# S7CAS-PLEIADES-CARTE-MERE_Pxx_ARBRE_CAP_.net
KiCad netlist of a schematic drawn in Altium Designer
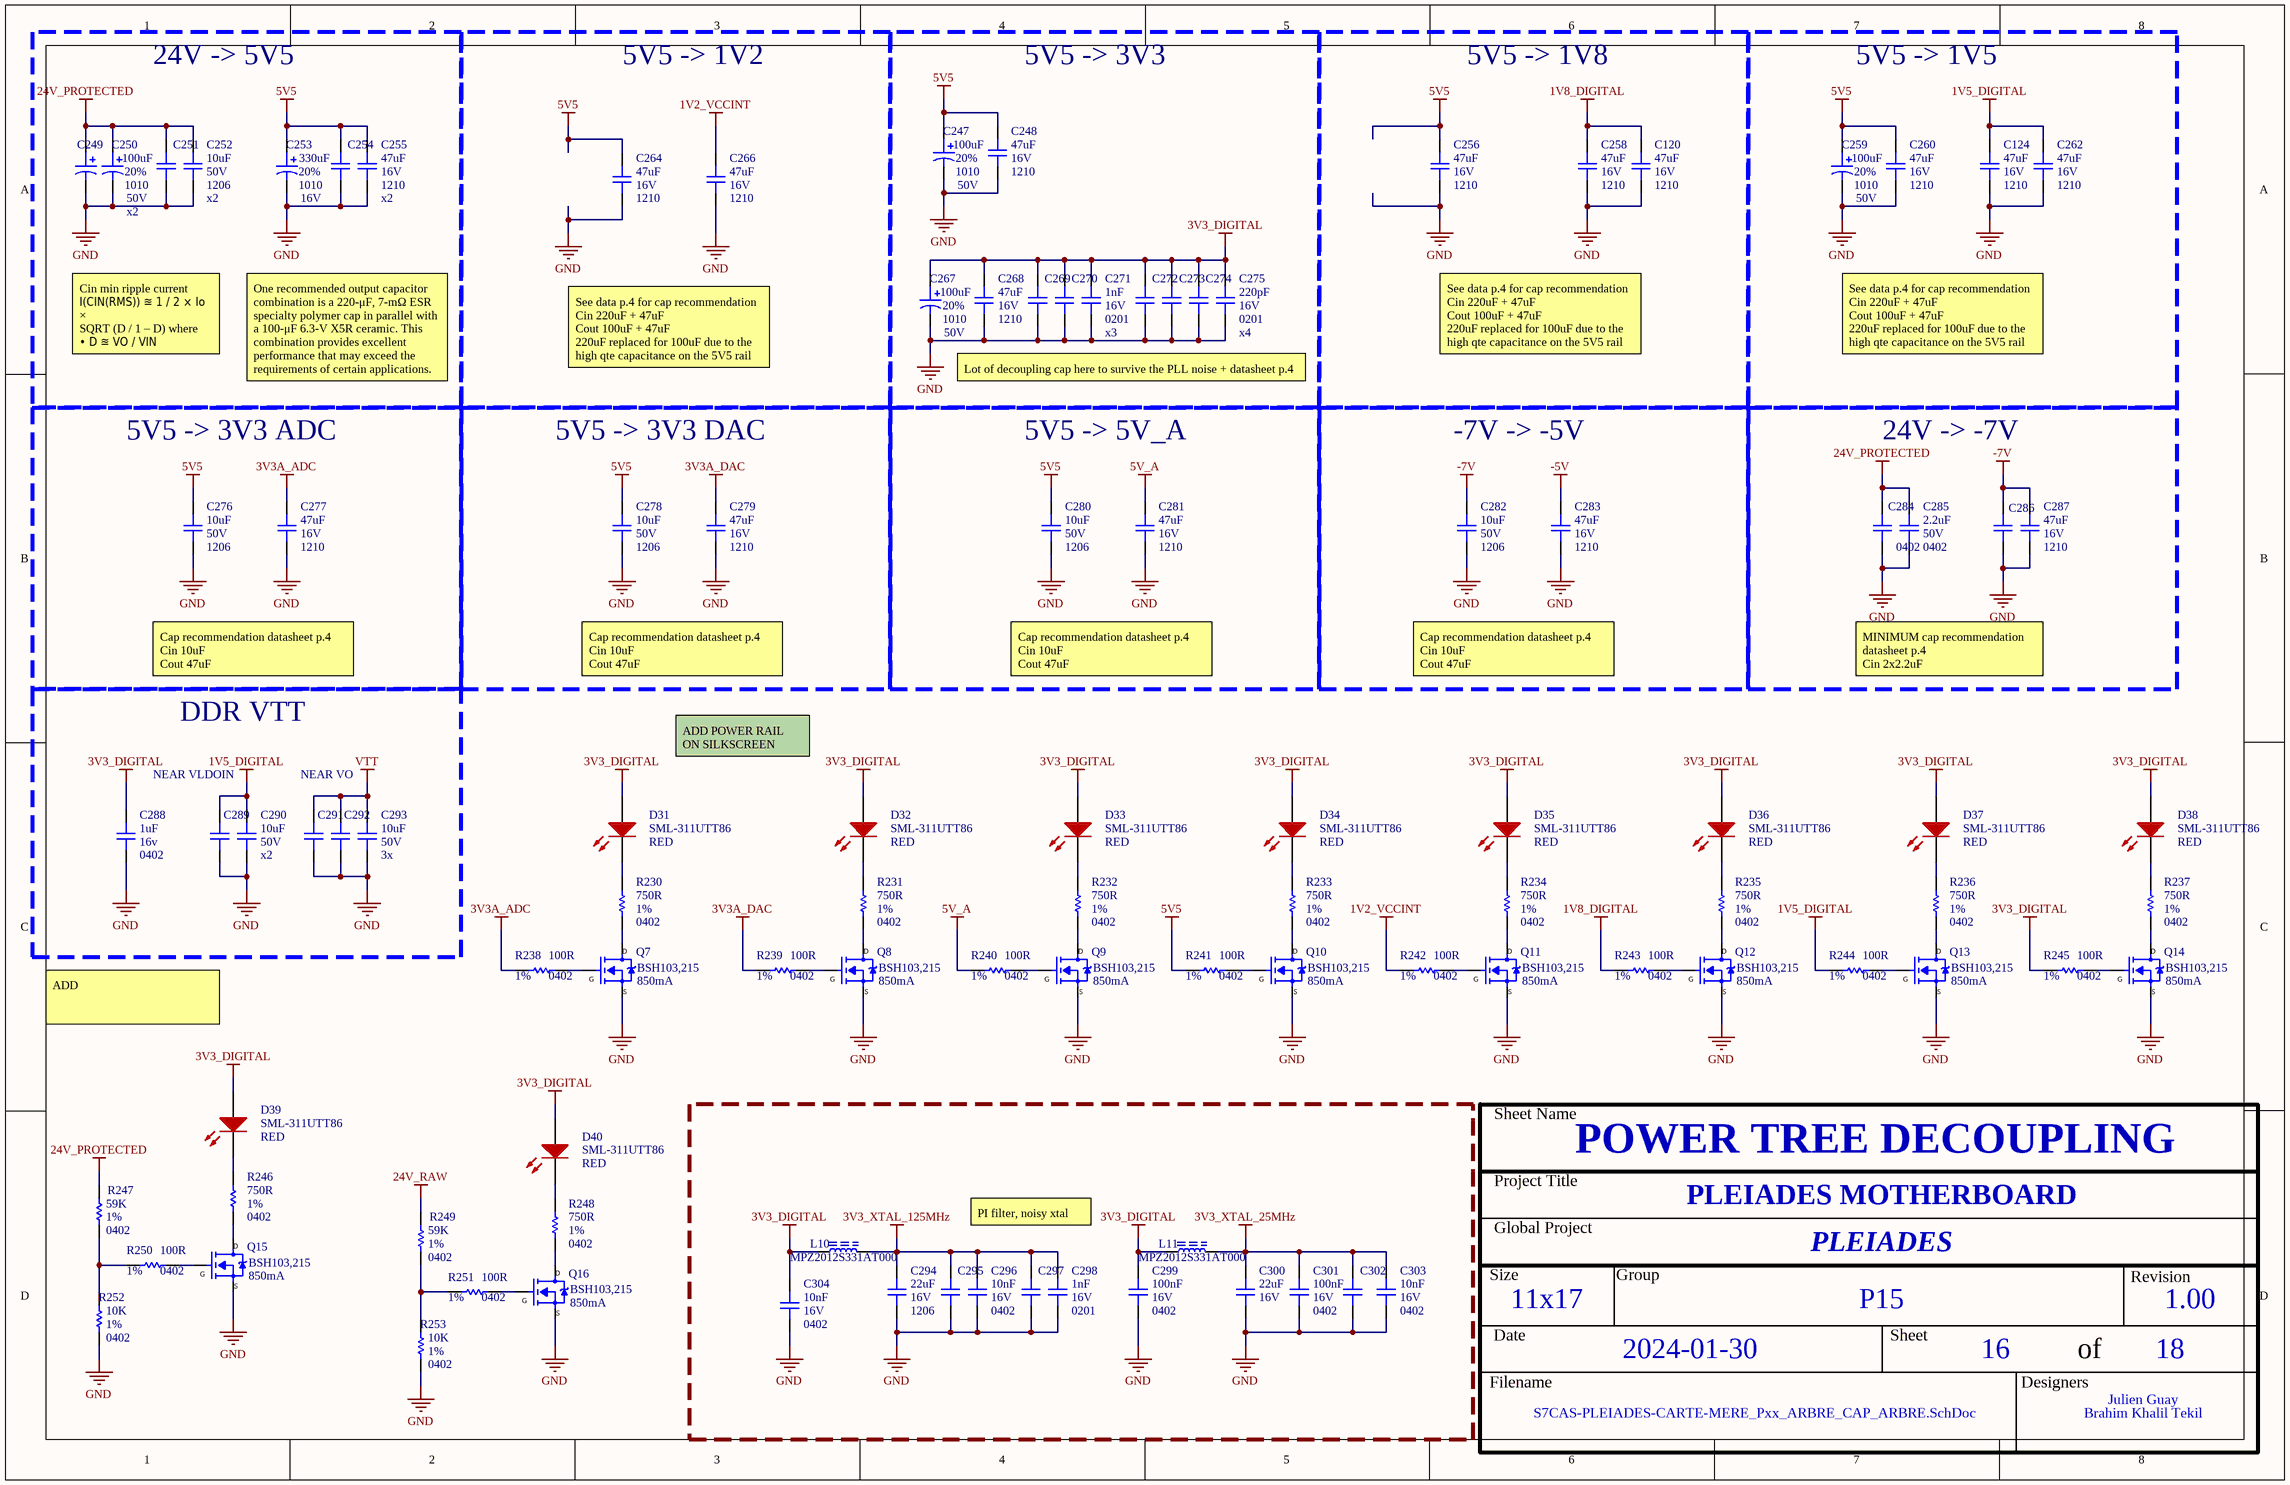
[diagram p0: S7CAS-PLEIADES-CARTE-MERE_Pxx_ARBRE_CAP_ARBRE.SchDoc]

(export (version "E")
  (design (tool "Eeschema 10.0.6"))
  (components
    (comp (ref "C120")
      (value "47uF")
      (footprint "CAP_1210")
      (description "CAP - 1210")
      (fields
        (field (name "VOLTAGE") "16V")
        (field (name "PACKAGE") "1210")
        (field (name "CREATEDBY") "Jonathan Bouchard")
      )
      (libsource (lib "S7CAS_LIB2023") (part "CAP - 1210"))
    )
    (comp (ref "C124")
      (value "47uF")
      (footprint "CAP_1210")
      (description "CAP - 1210")
      (fields
        (field (name "VOLTAGE") "16V")
        (field (name "PACKAGE") "1210")
        (field (name "CREATEDBY") "Jonathan Bouchard")
      )
      (libsource (lib "S7CAS_LIB2023") (part "CAP - 1210"))
    )
    (comp (ref "C247")
      (value "100uF")
      (footprint "CAP_ALU_1010_vishay")
      (description "CAP - ALU 100uF 20% 50V - 1010")
      (fields
        (field (name "MFG") "Vishay Dale")
        (field (name "MFG PART NUMBER") "MAL215099101E3")
        (field (name "VOLTAGE") "50V")
        (field (name "PACKAGE") "1010")
        (field (name "PRECISION") "20%")
        (field (name "CREATEDBY") "Jonathan Bouchard")
      )
      (libsource (lib "S7CAS_LIB2023") (part "CAP_ALU_MAL215099101E3"))
    )
    (comp (ref "C248")
      (value "47uF")
      (footprint "CAP_1210")
      (description "CAP - 1210")
      (fields
        (field (name "VOLTAGE") "16V")
        (field (name "PACKAGE") "1210")
        (field (name "CREATEDBY") "Jonathan Bouchard")
      )
      (libsource (lib "S7CAS_LIB2023") (part "CAP - 1210"))
    )
    (comp (ref "C249")
      (value "MAL215099101E3")
      (footprint "CAP_ALU_1010_vishay")
      (description "CAP - ALU 100uF 20% 50V - 1010")
      (fields (field (name "MFG") "Vishay Dale") (field (name "CREATEDBY") "Jonathan Bouchard"))
      (libsource (lib "S7CAS_LIB2023") (part "CAP_ALU_MAL215099101E3"))
    )
    (comp (ref "C250")
      (value "100uF")
      (footprint "CAP_ALU_1010_vishay")
      (description "CAP - ALU 100uF 20% 50V - 1010")
      (fields
        (field (name "MFG") "Vishay Dale")
        (field (name "MFG PART NUMBER") "MAL215099101E3")
        (field (name "VOLTAGE") "50V")
        (field (name "PACKAGE") "1010")
        (field (name "PRECISION") "20%")
        (field (name "CREATEDBY") "Jonathan Bouchard")
      )
      (libsource (lib "S7CAS_LIB2023") (part "CAP_ALU_MAL215099101E3"))
    )
    (comp (ref "C251")
      (value "CAP - 1206")
      (footprint "S7CAS_LIB2023:CAP_1206")
      (fields (field (name "VOLTAGE") "50V") (field (name "CREATEDBY") "Jonathan Bouchard"))
      (libsource (lib "S7CAS_LIB2023") (part "CAP - 1206"))
    )
    (comp (ref "C252")
      (value "10uF")
      (footprint "S7CAS_LIB2023:CAP_1206")
      (description "CAP - 1206")
      (fields
        (field (name "VOLTAGE") "50V")
        (field (name "PACKAGE") "1206")
        (field (name "CREATEDBY") "Jonathan Bouchard")
      )
      (libsource (lib "S7CAS_LIB2023") (part "CAP - 1206"))
    )
    (comp (ref "C253")
      (value "330uF")
      (footprint "CAP_ALU_1010_vishay")
      (description "CAP - ALU 330uF 20% 16V - 1010")
      (fields
        (field (name "MFG") "Vishay Dale")
        (field (name "MFG PART NUMBER") "MAL214699501E3")
        (field (name "VOLTAGE") "16V")
        (field (name "PACKAGE") "1010")
        (field (name "PRECISION") "20%")
        (field (name "CREATEDBY") "Jonathan Bouchard")
      )
      (libsource (lib "S7CAS_LIB2023") (part "CAP_ALU_MAL214699501E3"))
    )
    (comp (ref "C254")
      (value "CAP - 1210")
      (footprint "CAP_1210")
      (fields (field (name "VOLTAGE") "16V") (field (name "CREATEDBY") "Jonathan Bouchard"))
      (libsource (lib "S7CAS_LIB2023") (part "CAP - 1210"))
    )
    (comp (ref "C255")
      (value "47uF")
      (footprint "CAP_1210")
      (description "CAP - 1210")
      (fields
        (field (name "VOLTAGE") "16V")
        (field (name "PACKAGE") "1210")
        (field (name "CREATEDBY") "Jonathan Bouchard")
      )
      (libsource (lib "S7CAS_LIB2023") (part "CAP - 1210"))
    )
    (comp (ref "C256")
      (value "47uF")
      (footprint "CAP_1210")
      (description "CAP - 1210")
      (fields
        (field (name "VOLTAGE") "16V")
        (field (name "PACKAGE") "1210")
        (field (name "CREATEDBY") "Jonathan Bouchard")
      )
      (libsource (lib "S7CAS_LIB2023") (part "CAP - 1210"))
    )
    (comp (ref "C258")
      (value "47uF")
      (footprint "CAP_1210")
      (description "CAP - 1210")
      (fields
        (field (name "VOLTAGE") "16V")
        (field (name "PACKAGE") "1210")
        (field (name "CREATEDBY") "Jonathan Bouchard")
      )
      (libsource (lib "S7CAS_LIB2023") (part "CAP - 1210"))
    )
    (comp (ref "C259")
      (value "100uF")
      (footprint "CAP_ALU_1010_vishay")
      (description "CAP - ALU 100uF 20% 50V - 1010")
      (fields
        (field (name "MFG") "Vishay Dale")
        (field (name "MFG PART NUMBER") "MAL215099101E3")
        (field (name "VOLTAGE") "50V")
        (field (name "PACKAGE") "1010")
        (field (name "PRECISION") "20%")
        (field (name "CREATEDBY") "Jonathan Bouchard")
      )
      (libsource (lib "S7CAS_LIB2023") (part "CAP_ALU_MAL215099101E3"))
    )
    (comp (ref "C260")
      (value "47uF")
      (footprint "CAP_1210")
      (description "CAP - 1210")
      (fields
        (field (name "VOLTAGE") "16V")
        (field (name "PACKAGE") "1210")
        (field (name "CREATEDBY") "Jonathan Bouchard")
      )
      (libsource (lib "S7CAS_LIB2023") (part "CAP - 1210"))
    )
    (comp (ref "C262")
      (value "47uF")
      (footprint "CAP_1210")
      (description "CAP - 1210")
      (fields
        (field (name "VOLTAGE") "16V")
        (field (name "PACKAGE") "1210")
        (field (name "CREATEDBY") "Jonathan Bouchard")
      )
      (libsource (lib "S7CAS_LIB2023") (part "CAP - 1210"))
    )
    (comp (ref "C264")
      (value "47uF")
      (footprint "CAP_1210")
      (description "CAP - 1210")
      (fields
        (field (name "VOLTAGE") "16V")
        (field (name "PACKAGE") "1210")
        (field (name "CREATEDBY") "Jonathan Bouchard")
      )
      (libsource (lib "S7CAS_LIB2023") (part "CAP - 1210"))
    )
    (comp (ref "C266")
      (value "47uF")
      (footprint "CAP_1210")
      (description "CAP - 1210")
      (fields
        (field (name "VOLTAGE") "16V")
        (field (name "PACKAGE") "1210")
        (field (name "CREATEDBY") "Jonathan Bouchard")
      )
      (libsource (lib "S7CAS_LIB2023") (part "CAP - 1210"))
    )
    (comp (ref "C267")
      (value "100uF")
      (footprint "CAP_ALU_1010_vishay")
      (description "CAP - ALU 100uF 20% 50V - 1010")
      (fields
        (field (name "MFG") "Vishay Dale")
        (field (name "MFG PART NUMBER") "MAL215099101E3")
        (field (name "VOLTAGE") "50V")
        (field (name "PACKAGE") "1010")
        (field (name "PRECISION") "20%")
        (field (name "CREATEDBY") "Jonathan Bouchard")
      )
      (libsource (lib "S7CAS_LIB2023") (part "CAP_ALU_MAL215099101E3"))
    )
    (comp (ref "C268")
      (value "47uF")
      (footprint "CAP_1210")
      (description "CAP - 1210")
      (fields
        (field (name "VOLTAGE") "16V")
        (field (name "PACKAGE") "1210")
        (field (name "CREATEDBY") "Jonathan Bouchard")
      )
      (libsource (lib "S7CAS_LIB2023") (part "CAP - 1210"))
    )
    (comp (ref "C269")
      (value "CAP - 0201")
      (footprint "CAP_0201")
      (fields (field (name "VOLTAGE") "16V") (field (name "CREATEDBY") "Jonathan Bouchard"))
      (libsource (lib "S7CAS_LIB2023") (part "CAP - 0201"))
    )
    (comp (ref "C270")
      (value "CAP - 0201")
      (footprint "CAP_0201")
      (fields (field (name "VOLTAGE") "16V") (field (name "CREATEDBY") "Jonathan Bouchard"))
      (libsource (lib "S7CAS_LIB2023") (part "CAP - 0201"))
    )
    (comp (ref "C271")
      (value "1nF")
      (footprint "CAP_0201")
      (description "CAP - 0201")
      (fields
        (field (name "VOLTAGE") "16V")
        (field (name "PACKAGE") "0201")
        (field (name "CREATEDBY") "Jonathan Bouchard")
      )
      (libsource (lib "S7CAS_LIB2023") (part "CAP - 0201"))
    )
    (comp (ref "C272")
      (value "CAP - 0201")
      (footprint "CAP_0201")
      (fields (field (name "VOLTAGE") "16V") (field (name "CREATEDBY") "Jonathan Bouchard"))
      (libsource (lib "S7CAS_LIB2023") (part "CAP - 0201"))
    )
    (comp (ref "C273")
      (value "CAP - 0201")
      (footprint "CAP_0201")
      (fields (field (name "VOLTAGE") "16V") (field (name "CREATEDBY") "Jonathan Bouchard"))
      (libsource (lib "S7CAS_LIB2023") (part "CAP - 0201"))
    )
    (comp (ref "C274")
      (value "CAP - 0201")
      (footprint "CAP_0201")
      (fields (field (name "VOLTAGE") "16V") (field (name "CREATEDBY") "Jonathan Bouchard"))
      (libsource (lib "S7CAS_LIB2023") (part "CAP - 0201"))
    )
    (comp (ref "C275")
      (value "220pF")
      (footprint "CAP_0201")
      (description "CAP - 0201")
      (fields
        (field (name "VOLTAGE") "16V")
        (field (name "PACKAGE") "0201")
        (field (name "CREATEDBY") "Jonathan Bouchard")
      )
      (libsource (lib "S7CAS_LIB2023") (part "CAP - 0201"))
    )
    (comp (ref "C276")
      (value "10uF")
      (footprint "S7CAS_LIB2023:CAP_1206")
      (description "CAP - 1206")
      (fields
        (field (name "VOLTAGE") "50V")
        (field (name "PACKAGE") "1206")
        (field (name "CREATEDBY") "Jonathan Bouchard")
      )
      (libsource (lib "S7CAS_LIB2023") (part "CAP - 1206"))
    )
    (comp (ref "C277")
      (value "47uF")
      (footprint "CAP_1210")
      (description "CAP - 1210")
      (fields
        (field (name "VOLTAGE") "16V")
        (field (name "PACKAGE") "1210")
        (field (name "CREATEDBY") "Jonathan Bouchard")
      )
      (libsource (lib "S7CAS_LIB2023") (part "CAP - 1210"))
    )
    (comp (ref "C278")
      (value "10uF")
      (footprint "S7CAS_LIB2023:CAP_1206")
      (description "CAP - 1206")
      (fields
        (field (name "VOLTAGE") "50V")
        (field (name "PACKAGE") "1206")
        (field (name "CREATEDBY") "Jonathan Bouchard")
      )
      (libsource (lib "S7CAS_LIB2023") (part "CAP - 1206"))
    )
    (comp (ref "C279")
      (value "47uF")
      (footprint "CAP_1210")
      (description "CAP - 1210")
      (fields
        (field (name "VOLTAGE") "16V")
        (field (name "PACKAGE") "1210")
        (field (name "CREATEDBY") "Jonathan Bouchard")
      )
      (libsource (lib "S7CAS_LIB2023") (part "CAP - 1210"))
    )
    (comp (ref "C280")
      (value "10uF")
      (footprint "S7CAS_LIB2023:CAP_1206")
      (description "CAP - 1206")
      (fields
        (field (name "VOLTAGE") "50V")
        (field (name "PACKAGE") "1206")
        (field (name "CREATEDBY") "Jonathan Bouchard")
      )
      (libsource (lib "S7CAS_LIB2023") (part "CAP - 1206"))
    )
    (comp (ref "C281")
      (value "47uF")
      (footprint "CAP_1210")
      (description "CAP - 1210")
      (fields
        (field (name "VOLTAGE") "16V")
        (field (name "PACKAGE") "1210")
        (field (name "CREATEDBY") "Jonathan Bouchard")
      )
      (libsource (lib "S7CAS_LIB2023") (part "CAP - 1210"))
    )
    (comp (ref "C282")
      (value "10uF")
      (footprint "S7CAS_LIB2023:CAP_1206")
      (description "CAP - 1206")
      (fields
        (field (name "VOLTAGE") "50V")
        (field (name "PACKAGE") "1206")
        (field (name "CREATEDBY") "Jonathan Bouchard")
      )
      (libsource (lib "S7CAS_LIB2023") (part "CAP - 1206"))
    )
    (comp (ref "C283")
      (value "47uF")
      (footprint "CAP_1210")
      (description "CAP - 1210")
      (fields
        (field (name "VOLTAGE") "16V")
        (field (name "PACKAGE") "1210")
        (field (name "CREATEDBY") "Jonathan Bouchard")
      )
      (libsource (lib "S7CAS_LIB2023") (part "CAP - 1210"))
    )
    (comp (ref "C284")
      (value "CAP - 0402")
      (footprint "S7CAS_LIB2023:CAP_0402")
      (fields
        (field (name "VOLTAGE") "50V")
        (field (name "PACKAGE") "0402")
        (field (name "CREATEDBY") "Jonathan Bouchard")
      )
      (libsource (lib "S7CAS_LIB2023") (part "CAP - 0603"))
    )
    (comp (ref "C285")
      (value "2.2uF")
      (footprint "S7CAS_LIB2023:CAP_0402")
      (description "CAP - 0402")
      (fields
        (field (name "VOLTAGE") "50V")
        (field (name "PACKAGE") "0402")
        (field (name "CREATEDBY") "Jonathan Bouchard")
      )
      (libsource (lib "S7CAS_LIB2023") (part "CAP - 0603"))
    )
    (comp (ref "C286")
      (value "CAP - 1210")
      (footprint "CAP_1210")
      (fields (field (name "VOLTAGE") "16V") (field (name "CREATEDBY") "Jonathan Bouchard"))
      (libsource (lib "S7CAS_LIB2023") (part "CAP - 1210"))
    )
    (comp (ref "C287")
      (value "47uF")
      (footprint "CAP_1210")
      (description "CAP - 1210")
      (fields
        (field (name "VOLTAGE") "16V")
        (field (name "PACKAGE") "1210")
        (field (name "CREATEDBY") "Jonathan Bouchard")
      )
      (libsource (lib "S7CAS_LIB2023") (part "CAP - 1210"))
    )
    (comp (ref "C288")
      (value "1uF")
      (footprint "S7CAS_LIB2023:CAP_0402")
      (description "CAP - 0402")
      (fields
        (field (name "VOLTAGE") "16v")
        (field (name "PACKAGE") "0402")
        (field (name "CREATEDBY") "Jonathan Bouchard")
      )
      (libsource (lib "S7CAS_LIB2023") (part "CAP - 0603"))
    )
    (comp (ref "C289")
      (value "CAP - 0805")
      (footprint "CAP_0805")
      (fields (field (name "VOLTAGE") "50V") (field (name "CREATEDBY") "Jonathan Bouchard"))
      (libsource (lib "S7CAS_LIB2023") (part "CAP - 0805"))
    )
    (comp (ref "C290")
      (value "10uF")
      (footprint "CAP_0805")
      (description "CAP - 0805")
      (fields (field (name "VOLTAGE") "50V") (field (name "CREATEDBY") "Jonathan Bouchard"))
      (libsource (lib "S7CAS_LIB2023") (part "CAP - 0805"))
    )
    (comp (ref "C291")
      (value "CAP - 0805")
      (footprint "CAP_0805")
      (fields (field (name "VOLTAGE") "50V") (field (name "CREATEDBY") "Jonathan Bouchard"))
      (libsource (lib "S7CAS_LIB2023") (part "CAP - 0805"))
    )
    (comp (ref "C292")
      (value "CAP - 0805")
      (footprint "CAP_0805")
      (fields (field (name "VOLTAGE") "50V") (field (name "CREATEDBY") "Jonathan Bouchard"))
      (libsource (lib "S7CAS_LIB2023") (part "CAP - 0805"))
    )
    (comp (ref "C293")
      (value "10uF")
      (footprint "CAP_0805")
      (description "CAP - 0805")
      (fields (field (name "VOLTAGE") "50V") (field (name "CREATEDBY") "Jonathan Bouchard"))
      (libsource (lib "S7CAS_LIB2023") (part "CAP - 0805"))
    )
    (comp (ref "C294")
      (value "22uF")
      (footprint "S7CAS_LIB2023:CAP_1206")
      (description "CAP - 1206")
      (fields
        (field (name "VOLTAGE") "16V")
        (field (name "PACKAGE") "1206")
        (field (name "CREATEDBY") "Jonathan Bouchard")
      )
      (libsource (lib "S7CAS_LIB2023") (part "CAP - 1206"))
    )
    (comp (ref "C295")
      (value "CAP - 0402")
      (footprint "CAP_0402")
      (fields (field (name "VOLTAGE") "16V") (field (name "CREATEDBY") "Jonathan Bouchard"))
      (libsource (lib "S7CAS_LIB2023") (part "CAP - 0402"))
    )
    (comp (ref "C296")
      (value "10nF")
      (footprint "CAP_0402")
      (description "CAP - 0402")
      (fields
        (field (name "VOLTAGE") "16V")
        (field (name "PACKAGE") "0402")
        (field (name "CREATEDBY") "Jonathan Bouchard")
      )
      (libsource (lib "S7CAS_LIB2023") (part "CAP - 0402"))
    )
    (comp (ref "C297")
      (value "CAP - 0201")
      (footprint "CAP_0201")
      (fields (field (name "VOLTAGE") "16V") (field (name "CREATEDBY") "Jonathan Bouchard"))
      (libsource (lib "S7CAS_LIB2023") (part "CAP - 0201"))
    )
    (comp (ref "C298")
      (value "1nF")
      (footprint "CAP_0201")
      (description "CAP - 0201")
      (fields
        (field (name "VOLTAGE") "16V")
        (field (name "PACKAGE") "0201")
        (field (name "CREATEDBY") "Jonathan Bouchard")
      )
      (libsource (lib "S7CAS_LIB2023") (part "CAP - 0201"))
    )
    (comp (ref "C299")
      (value "100nF")
      (footprint "S7CAS_LIB2023:CAP_0402")
      (description "CAP - 0402")
      (fields
        (field (name "VOLTAGE") "16V")
        (field (name "PACKAGE") "0402")
        (field (name "CREATEDBY") "Jonathan Bouchard")
      )
      (libsource (lib "S7CAS_LIB2023") (part "CAP - 0603"))
    )
    (comp (ref "C300")
      (value "22uF")
      (footprint "S7CAS_LIB2023:CAP_1206")
      (description "CAP - 1206")
      (fields (field (name "VOLTAGE") "16V") (field (name "CREATEDBY") "Jonathan Bouchard"))
      (libsource (lib "S7CAS_LIB2023") (part "CAP - 1206"))
    )
    (comp (ref "C301")
      (value "100nF")
      (footprint "S7CAS_LIB2023:CAP_0402")
      (description "CAP - 0402")
      (fields
        (field (name "VOLTAGE") "16V")
        (field (name "PACKAGE") "0402")
        (field (name "CREATEDBY") "Jonathan Bouchard")
      )
      (libsource (lib "S7CAS_LIB2023") (part "CAP - 0603"))
    )
    (comp (ref "C302")
      (value "CAP - 0402")
      (footprint "CAP_0402")
      (fields (field (name "VOLTAGE") "16V") (field (name "CREATEDBY") "Jonathan Bouchard"))
      (libsource (lib "S7CAS_LIB2023") (part "CAP - 0402"))
    )
    (comp (ref "C303")
      (value "10nF")
      (footprint "CAP_0402")
      (description "CAP - 0402")
      (fields
        (field (name "VOLTAGE") "16V")
        (field (name "PACKAGE") "0402")
        (field (name "CREATEDBY") "Jonathan Bouchard")
      )
      (libsource (lib "S7CAS_LIB2023") (part "CAP - 0402"))
    )
    (comp (ref "C304")
      (value "10nF")
      (footprint "CAP_0402")
      (description "CAP - 0402")
      (fields
        (field (name "VOLTAGE") "16V")
        (field (name "PACKAGE") "0402")
        (field (name "CREATEDBY") "Jonathan Bouchard")
      )
      (libsource (lib "S7CAS_LIB2023") (part "CAP - 0402"))
    )
    (comp (ref "D31")
      (value "SML-311UTT86")
      (footprint "LED_0603")
      (description "LED - 620nM RED 2mA - 0603")
      (fields
        (field (name "VOLTAGE") "1.8V")
        (field (name "MFG") "ROHM Semiconductor")
        (field (name "ALTIUM_VALUE") "RED")
        (field (name "CREATEDBY") "Jonathan Bouchard")
      )
      (libsource (lib "S7CAS_LIB2023") (part "LED_SML-311UTT86"))
    )
    (comp (ref "D32")
      (value "SML-311UTT86")
      (footprint "LED_0603")
      (description "LED - 620nM RED 2mA - 0603")
      (fields
        (field (name "VOLTAGE") "1.8V")
        (field (name "MFG") "ROHM Semiconductor")
        (field (name "ALTIUM_VALUE") "RED")
        (field (name "CREATEDBY") "Jonathan Bouchard")
      )
      (libsource (lib "S7CAS_LIB2023") (part "LED_SML-311UTT86"))
    )
    (comp (ref "D33")
      (value "SML-311UTT86")
      (footprint "LED_0603")
      (description "LED - 620nM RED 2mA - 0603")
      (fields
        (field (name "VOLTAGE") "1.8V")
        (field (name "MFG") "ROHM Semiconductor")
        (field (name "ALTIUM_VALUE") "RED")
        (field (name "CREATEDBY") "Jonathan Bouchard")
      )
      (libsource (lib "S7CAS_LIB2023") (part "LED_SML-311UTT86"))
    )
    (comp (ref "D34")
      (value "SML-311UTT86")
      (footprint "LED_0603")
      (description "LED - 620nM RED 2mA - 0603")
      (fields
        (field (name "VOLTAGE") "1.8V")
        (field (name "MFG") "ROHM Semiconductor")
        (field (name "ALTIUM_VALUE") "RED")
        (field (name "CREATEDBY") "Jonathan Bouchard")
      )
      (libsource (lib "S7CAS_LIB2023") (part "LED_SML-311UTT86"))
    )
    (comp (ref "D35")
      (value "SML-311UTT86")
      (footprint "LED_0603")
      (description "LED - 620nM RED 2mA - 0603")
      (fields
        (field (name "VOLTAGE") "1.8V")
        (field (name "MFG") "ROHM Semiconductor")
        (field (name "ALTIUM_VALUE") "RED")
        (field (name "CREATEDBY") "Jonathan Bouchard")
      )
      (libsource (lib "S7CAS_LIB2023") (part "LED_SML-311UTT86"))
    )
    (comp (ref "D36")
      (value "SML-311UTT86")
      (footprint "LED_0603")
      (description "LED - 620nM RED 2mA - 0603")
      (fields
        (field (name "VOLTAGE") "1.8V")
        (field (name "MFG") "ROHM Semiconductor")
        (field (name "ALTIUM_VALUE") "RED")
        (field (name "CREATEDBY") "Jonathan Bouchard")
      )
      (libsource (lib "S7CAS_LIB2023") (part "LED_SML-311UTT86"))
    )
    (comp (ref "D37")
      (value "SML-311UTT86")
      (footprint "LED_0603")
      (description "LED - 620nM RED 2mA - 0603")
      (fields
        (field (name "VOLTAGE") "1.8V")
        (field (name "MFG") "ROHM Semiconductor")
        (field (name "ALTIUM_VALUE") "RED")
        (field (name "CREATEDBY") "Jonathan Bouchard")
      )
      (libsource (lib "S7CAS_LIB2023") (part "LED_SML-311UTT86"))
    )
    (comp (ref "D38")
      (value "SML-311UTT86")
      (footprint "LED_0603")
      (description "LED - 620nM RED 2mA - 0603")
      (fields
        (field (name "VOLTAGE") "1.8V")
        (field (name "MFG") "ROHM Semiconductor")
        (field (name "ALTIUM_VALUE") "RED")
        (field (name "CREATEDBY") "Jonathan Bouchard")
      )
      (libsource (lib "S7CAS_LIB2023") (part "LED_SML-311UTT86"))
    )
    (comp (ref "D39")
      (value "SML-311UTT86")
      (footprint "LED_0603")
      (description "LED - 620nM RED 2mA - 0603")
      (fields
        (field (name "VOLTAGE") "1.8V")
        (field (name "MFG") "ROHM Semiconductor")
        (field (name "ALTIUM_VALUE") "RED")
        (field (name "CREATEDBY") "Jonathan Bouchard")
      )
      (libsource (lib "S7CAS_LIB2023") (part "LED_SML-311UTT86"))
    )
    (comp (ref "D40")
      (value "SML-311UTT86")
      (footprint "LED_0603")
      (description "LED - 620nM RED 2mA - 0603")
      (fields
        (field (name "VOLTAGE") "1.8V")
        (field (name "MFG") "ROHM Semiconductor")
        (field (name "ALTIUM_VALUE") "RED")
        (field (name "CREATEDBY") "Jonathan Bouchard")
      )
      (libsource (lib "S7CAS_LIB2023") (part "LED_SML-311UTT86"))
    )
    (comp (ref "L10")
      (value "FER - 0805")
      (footprint "S7CAS_LIB2023:FER_0805")
      (fields
        (field (name "MFG") "TDK Corporation")
        (field (name "MFG PART NUMBER") "MPZ2012S331AT000")
        (field (name "CREATEDBY") "Jonathan Bouchard")
      )
      (libsource (lib "S7CAS_LIB2023") (part "FER - 0805"))
    )
    (comp (ref "L11")
      (value "FER - 0805")
      (footprint "S7CAS_LIB2023:FER_0805")
      (fields
        (field (name "MFG") "TDK Corporation")
        (field (name "MFG PART NUMBER") "MPZ2012S331AT000")
        (field (name "CREATEDBY") "Jonathan Bouchard")
      )
      (libsource (lib "S7CAS_LIB2023") (part "FER - 0805"))
    )
    (comp (ref "Q7")
      (value "BSH103,215")
      (footprint "SOT23-3")
      (description "N-Channel  Enhancement Mode Field Effect Transistor")
      (fields (field (name "CURRENT") "850mA"))
      (libsource (lib "S7CAS_LIB2023") (part "MOS_N_CHANNEL"))
    )
    (comp (ref "Q8")
      (value "BSH103,215")
      (footprint "SOT23-3")
      (description "N-Channel  Enhancement Mode Field Effect Transistor")
      (fields (field (name "CURRENT") "850mA"))
      (libsource (lib "S7CAS_LIB2023") (part "MOS_N_CHANNEL"))
    )
    (comp (ref "Q9")
      (value "BSH103,215")
      (footprint "SOT23-3")
      (description "N-Channel  Enhancement Mode Field Effect Transistor")
      (fields (field (name "CURRENT") "850mA"))
      (libsource (lib "S7CAS_LIB2023") (part "MOS_N_CHANNEL"))
    )
    (comp (ref "Q10")
      (value "BSH103,215")
      (footprint "SOT23-3")
      (description "N-Channel  Enhancement Mode Field Effect Transistor")
      (fields (field (name "CURRENT") "850mA"))
      (libsource (lib "S7CAS_LIB2023") (part "MOS_N_CHANNEL"))
    )
    (comp (ref "Q11")
      (value "BSH103,215")
      (footprint "SOT23-3")
      (description "N-Channel  Enhancement Mode Field Effect Transistor")
      (fields (field (name "CURRENT") "850mA"))
      (libsource (lib "S7CAS_LIB2023") (part "MOS_N_CHANNEL"))
    )
    (comp (ref "Q12")
      (value "BSH103,215")
      (footprint "SOT23-3")
      (description "N-Channel  Enhancement Mode Field Effect Transistor")
      (fields (field (name "CURRENT") "850mA"))
      (libsource (lib "S7CAS_LIB2023") (part "MOS_N_CHANNEL"))
    )
    (comp (ref "Q13")
      (value "BSH103,215")
      (footprint "SOT23-3")
      (description "N-Channel  Enhancement Mode Field Effect Transistor")
      (fields (field (name "CURRENT") "850mA"))
      (libsource (lib "S7CAS_LIB2023") (part "MOS_N_CHANNEL"))
    )
    (comp (ref "Q14")
      (value "BSH103,215")
      (footprint "SOT23-3")
      (description "N-Channel  Enhancement Mode Field Effect Transistor")
      (fields (field (name "CURRENT") "850mA"))
      (libsource (lib "S7CAS_LIB2023") (part "MOS_N_CHANNEL"))
    )
    (comp (ref "Q15")
      (value "BSH103,215")
      (footprint "SOT23-3")
      (description "N-Channel  Enhancement Mode Field Effect Transistor")
      (fields (field (name "CURRENT") "850mA"))
      (libsource (lib "S7CAS_LIB2023") (part "MOS_N_CHANNEL"))
    )
    (comp (ref "Q16")
      (value "BSH103,215")
      (footprint "SOT23-3")
      (description "N-Channel  Enhancement Mode Field Effect Transistor")
      (fields (field (name "CURRENT") "850mA"))
      (libsource (lib "S7CAS_LIB2023") (part "MOS_N_CHANNEL"))
    )
    (comp (ref "R230")
      (value "750R")
      (footprint "S7CAS_LIB2023:RES_0402")
      (description "RES - 0402")
      (fields
        (field (name "PACKAGE") "0402")
        (field (name "PRECISION") "1%")
        (field (name "CREATEDBY") "Jonathan Bouchard")
      )
      (libsource (lib "S7CAS_LIB2023") (part "RES - 0603"))
    )
    (comp (ref "R231")
      (value "750R")
      (footprint "S7CAS_LIB2023:RES_0402")
      (description "RES - 0402")
      (fields
        (field (name "PACKAGE") "0402")
        (field (name "PRECISION") "1%")
        (field (name "CREATEDBY") "Jonathan Bouchard")
      )
      (libsource (lib "S7CAS_LIB2023") (part "RES - 0603"))
    )
    (comp (ref "R232")
      (value "750R")
      (footprint "S7CAS_LIB2023:RES_0402")
      (description "RES - 0402")
      (fields
        (field (name "PACKAGE") "0402")
        (field (name "PRECISION") "1%")
        (field (name "CREATEDBY") "Jonathan Bouchard")
      )
      (libsource (lib "S7CAS_LIB2023") (part "RES - 0603"))
    )
    (comp (ref "R233")
      (value "750R")
      (footprint "S7CAS_LIB2023:RES_0402")
      (description "RES - 0402")
      (fields
        (field (name "PACKAGE") "0402")
        (field (name "PRECISION") "1%")
        (field (name "CREATEDBY") "Jonathan Bouchard")
      )
      (libsource (lib "S7CAS_LIB2023") (part "RES - 0603"))
    )
    (comp (ref "R234")
      (value "750R")
      (footprint "S7CAS_LIB2023:RES_0402")
      (description "RES - 0402")
      (fields
        (field (name "PACKAGE") "0402")
        (field (name "PRECISION") "1%")
        (field (name "CREATEDBY") "Jonathan Bouchard")
      )
      (libsource (lib "S7CAS_LIB2023") (part "RES - 0603"))
    )
    (comp (ref "R235")
      (value "750R")
      (footprint "S7CAS_LIB2023:RES_0402")
      (description "RES - 0402")
      (fields
        (field (name "PACKAGE") "0402")
        (field (name "PRECISION") "1%")
        (field (name "CREATEDBY") "Jonathan Bouchard")
      )
      (libsource (lib "S7CAS_LIB2023") (part "RES - 0603"))
    )
    (comp (ref "R236")
      (value "750R")
      (footprint "S7CAS_LIB2023:RES_0402")
      (description "RES - 0402")
      (fields
        (field (name "PACKAGE") "0402")
        (field (name "PRECISION") "1%")
        (field (name "CREATEDBY") "Jonathan Bouchard")
      )
      (libsource (lib "S7CAS_LIB2023") (part "RES - 0603"))
    )
    (comp (ref "R237")
      (value "750R")
      (footprint "S7CAS_LIB2023:RES_0402")
      (description "RES - 0402")
      (fields
        (field (name "PACKAGE") "0402")
        (field (name "PRECISION") "1%")
        (field (name "CREATEDBY") "Jonathan Bouchard")
      )
      (libsource (lib "S7CAS_LIB2023") (part "RES - 0603"))
    )
    (comp (ref "R238")
      (value "100R")
      (footprint "S7CAS_LIB2023:RES_0402")
      (description "RES - 0402")
      (fields
        (field (name "PACKAGE") "0402")
        (field (name "PRECISION") "1%")
        (field (name "CREATEDBY") "Jonathan Bouchard")
      )
      (libsource (lib "S7CAS_LIB2023") (part "RES - 0603"))
    )
    (comp (ref "R239")
      (value "100R")
      (footprint "S7CAS_LIB2023:RES_0402")
      (description "RES - 0402")
      (fields
        (field (name "PACKAGE") "0402")
        (field (name "PRECISION") "1%")
        (field (name "CREATEDBY") "Jonathan Bouchard")
      )
      (libsource (lib "S7CAS_LIB2023") (part "RES - 0603"))
    )
    (comp (ref "R240")
      (value "100R")
      (footprint "S7CAS_LIB2023:RES_0402")
      (description "RES - 0402")
      (fields
        (field (name "PACKAGE") "0402")
        (field (name "PRECISION") "1%")
        (field (name "CREATEDBY") "Jonathan Bouchard")
      )
      (libsource (lib "S7CAS_LIB2023") (part "RES - 0603"))
    )
    (comp (ref "R241")
      (value "100R")
      (footprint "S7CAS_LIB2023:RES_0402")
      (description "RES - 0402")
      (fields
        (field (name "PACKAGE") "0402")
        (field (name "PRECISION") "1%")
        (field (name "CREATEDBY") "Jonathan Bouchard")
      )
      (libsource (lib "S7CAS_LIB2023") (part "RES - 0603"))
    )
    (comp (ref "R242")
      (value "100R")
      (footprint "S7CAS_LIB2023:RES_0402")
      (description "RES - 0402")
      (fields
        (field (name "PACKAGE") "0402")
        (field (name "PRECISION") "1%")
        (field (name "CREATEDBY") "Jonathan Bouchard")
      )
      (libsource (lib "S7CAS_LIB2023") (part "RES - 0603"))
    )
    (comp (ref "R243")
      (value "100R")
      (footprint "S7CAS_LIB2023:RES_0402")
      (description "RES - 0402")
      (fields
        (field (name "PACKAGE") "0402")
        (field (name "PRECISION") "1%")
        (field (name "CREATEDBY") "Jonathan Bouchard")
      )
      (libsource (lib "S7CAS_LIB2023") (part "RES - 0603"))
    )
    (comp (ref "R244")
      (value "100R")
      (footprint "S7CAS_LIB2023:RES_0402")
      (description "RES - 0402")
      (fields
        (field (name "PACKAGE") "0402")
        (field (name "PRECISION") "1%")
        (field (name "CREATEDBY") "Jonathan Bouchard")
      )
      (libsource (lib "S7CAS_LIB2023") (part "RES - 0603"))
    )
    (comp (ref "R245")
      (value "100R")
      (footprint "S7CAS_LIB2023:RES_0402")
      (description "RES - 0402")
      (fields
        (field (name "PACKAGE") "0402")
        (field (name "PRECISION") "1%")
        (field (name "CREATEDBY") "Jonathan Bouchard")
      )
      (libsource (lib "S7CAS_LIB2023") (part "RES - 0603"))
    )
    (comp (ref "R246")
      (value "750R")
      (footprint "S7CAS_LIB2023:RES_0402")
      (description "RES - 0402")
      (fields
        (field (name "PACKAGE") "0402")
        (field (name "PRECISION") "1%")
        (field (name "CREATEDBY") "Jonathan Bouchard")
      )
      (libsource (lib "S7CAS_LIB2023") (part "RES - 0603"))
    )
    (comp (ref "R247")
      (value "59K")
      (footprint "S7CAS_LIB2023:RES_0402")
      (description "RES - 0402")
      (fields
        (field (name "PACKAGE") "0402")
        (field (name "PRECISION") "1%")
        (field (name "CREATEDBY") "Jonathan Bouchard")
      )
      (libsource (lib "S7CAS_LIB2023") (part "RES - 0603"))
    )
    (comp (ref "R248")
      (value "750R")
      (footprint "S7CAS_LIB2023:RES_0402")
      (description "RES - 0402")
      (fields
        (field (name "PACKAGE") "0402")
        (field (name "PRECISION") "1%")
        (field (name "CREATEDBY") "Jonathan Bouchard")
      )
      (libsource (lib "S7CAS_LIB2023") (part "RES - 0603"))
    )
    (comp (ref "R249")
      (value "59K")
      (footprint "S7CAS_LIB2023:RES_0402")
      (description "RES - 0402")
      (fields
        (field (name "PACKAGE") "0402")
        (field (name "PRECISION") "1%")
        (field (name "CREATEDBY") "Jonathan Bouchard")
      )
      (libsource (lib "S7CAS_LIB2023") (part "RES - 0603"))
    )
    (comp (ref "R250")
      (value "100R")
      (footprint "S7CAS_LIB2023:RES_0402")
      (description "RES - 0402")
      (fields
        (field (name "PACKAGE") "0402")
        (field (name "PRECISION") "1%")
        (field (name "CREATEDBY") "Jonathan Bouchard")
      )
      (libsource (lib "S7CAS_LIB2023") (part "RES - 0603"))
    )
    (comp (ref "R251")
      (value "100R")
      (footprint "S7CAS_LIB2023:RES_0402")
      (description "RES - 0402")
      (fields
        (field (name "PACKAGE") "0402")
        (field (name "PRECISION") "1%")
        (field (name "CREATEDBY") "Jonathan Bouchard")
      )
      (libsource (lib "S7CAS_LIB2023") (part "RES - 0603"))
    )
    (comp (ref "R252")
      (value "10K")
      (footprint "S7CAS_LIB2023:RES_0402")
      (description "RES - 0402")
      (fields
        (field (name "PACKAGE") "0402")
        (field (name "PRECISION") "1%")
        (field (name "CREATEDBY") "Jonathan Bouchard")
      )
      (libsource (lib "S7CAS_LIB2023") (part "RES - 0603"))
    )
    (comp (ref "R253")
      (value "10K")
      (footprint "S7CAS_LIB2023:RES_0402")
      (description "RES - 0402")
      (fields
        (field (name "PACKAGE") "0402")
        (field (name "PRECISION") "1%")
        (field (name "CREATEDBY") "Jonathan Bouchard")
      )
      (libsource (lib "S7CAS_LIB2023") (part "RES - 0603"))
    )
  )
  (nets
    (net (code "1") (name "-5V") (class "Default")
      (node (ref "C283") (pin "2") (pinfunction "2_2") (pintype "passive"))
    )
    (net (code "2") (name "-7V") (class "Default")
      (node (ref "C282") (pin "2") (pinfunction "2_2") (pintype "passive"))
      (node (ref "C286") (pin "2") (pinfunction "2_2") (pintype "passive"))
      (node (ref "C287") (pin "2") (pinfunction "2_2") (pintype "passive"))
    )
    (net (code "3") (name "1V2_VCCINT") (class "Default")
      (node (ref "C266") (pin "2") (pinfunction "2_2") (pintype "passive"))
      (node (ref "R242") (pin "2") (pinfunction "2_2") (pintype "passive"))
    )
    (net (code "4") (name "1V5_DIGITAL") (class "Default")
      (node (ref "C124") (pin "2") (pinfunction "2_2") (pintype "passive"))
      (node (ref "C262") (pin "2") (pinfunction "2_2") (pintype "passive"))
      (node (ref "C289") (pin "2") (pinfunction "2_2") (pintype "passive"))
      (node (ref "C290") (pin "2") (pinfunction "2_2") (pintype "passive"))
      (node (ref "R244") (pin "2") (pinfunction "2_2") (pintype "passive"))
    )
    (net (code "5") (name "1V8_DIGITAL") (class "Default")
      (node (ref "C120") (pin "2") (pinfunction "2_2") (pintype "passive"))
      (node (ref "C258") (pin "2") (pinfunction "2_2") (pintype "passive"))
      (node (ref "R243") (pin "2") (pinfunction "2_2") (pintype "passive"))
    )
    (net (code "6") (name "3V3A_ADC") (class "Default")
      (node (ref "C277") (pin "2") (pinfunction "2_2") (pintype "passive"))
      (node (ref "R238") (pin "2") (pinfunction "2_2") (pintype "passive"))
    )
    (net (code "7") (name "3V3A_DAC") (class "Default")
      (node (ref "C279") (pin "2") (pinfunction "2_2") (pintype "passive"))
      (node (ref "R239") (pin "2") (pinfunction "2_2") (pintype "passive"))
    )
    (net (code "8") (name "3V3_DIGITAL") (class "Default")
      (node (ref "C267") (pin "1") (pinfunction "1_1") (pintype "passive"))
      (node (ref "C268") (pin "2") (pinfunction "2_2") (pintype "passive"))
      (node (ref "C269") (pin "2") (pinfunction "2_2") (pintype "passive"))
      (node (ref "C270") (pin "2") (pinfunction "2_2") (pintype "passive"))
      (node (ref "C271") (pin "2") (pinfunction "2_2") (pintype "passive"))
      (node (ref "C272") (pin "2") (pinfunction "2_2") (pintype "passive"))
      (node (ref "C273") (pin "2") (pinfunction "2_2") (pintype "passive"))
      (node (ref "C274") (pin "2") (pinfunction "2_2") (pintype "passive"))
      (node (ref "C275") (pin "2") (pinfunction "2_2") (pintype "passive"))
      (node (ref "C288") (pin "2") (pinfunction "2_2") (pintype "passive"))
      (node (ref "C299") (pin "2") (pinfunction "2_2") (pintype "passive"))
      (node (ref "C304") (pin "2") (pinfunction "2_2") (pintype "passive"))
      (node (ref "D31") (pin "A") (pinfunction "A_A") (pintype "passive"))
      (node (ref "D32") (pin "A") (pinfunction "A_A") (pintype "passive"))
      (node (ref "D33") (pin "A") (pinfunction "A_A") (pintype "passive"))
      (node (ref "D34") (pin "A") (pinfunction "A_A") (pintype "passive"))
      (node (ref "D35") (pin "A") (pinfunction "A_A") (pintype "passive"))
      (node (ref "D36") (pin "A") (pinfunction "A_A") (pintype "passive"))
      (node (ref "D37") (pin "A") (pinfunction "A_A") (pintype "passive"))
      (node (ref "D38") (pin "A") (pinfunction "A_A") (pintype "passive"))
      (node (ref "D39") (pin "A") (pinfunction "A_A") (pintype "passive"))
      (node (ref "D40") (pin "A") (pinfunction "A_A") (pintype "passive"))
      (node (ref "L10") (pin "2") (pinfunction "2_2") (pintype "passive"))
      (node (ref "L11") (pin "2") (pinfunction "2_2") (pintype "passive"))
      (node (ref "R245") (pin "2") (pinfunction "2_2") (pintype "passive"))
    )
    (net (code "9") (name "3V3_XTAL_25MHz") (class "Default")
      (node (ref "C300") (pin "2") (pinfunction "2_2") (pintype "passive"))
      (node (ref "C301") (pin "2") (pinfunction "2_2") (pintype "passive"))
      (node (ref "C302") (pin "2") (pinfunction "2_2") (pintype "passive"))
      (node (ref "C303") (pin "2") (pinfunction "2_2") (pintype "passive"))
      (node (ref "L11") (pin "1") (pinfunction "1_1") (pintype "passive"))
    )
    (net (code "10") (name "3V3_XTAL_125MHz") (class "Default")
      (node (ref "C294") (pin "2") (pinfunction "2_2") (pintype "passive"))
      (node (ref "C295") (pin "2") (pinfunction "2_2") (pintype "passive"))
      (node (ref "C296") (pin "2") (pinfunction "2_2") (pintype "passive"))
      (node (ref "C297") (pin "2") (pinfunction "2_2") (pintype "passive"))
      (node (ref "C298") (pin "2") (pinfunction "2_2") (pintype "passive"))
      (node (ref "L10") (pin "1") (pinfunction "1_1") (pintype "passive"))
    )
    (net (code "11") (name "5V5") (class "Default")
      (node (ref "C247") (pin "1") (pinfunction "1_1") (pintype "passive"))
      (node (ref "C248") (pin "2") (pinfunction "2_2") (pintype "passive"))
      (node (ref "C253") (pin "1") (pinfunction "1_1") (pintype "passive"))
      (node (ref "C254") (pin "2") (pinfunction "2_2") (pintype "passive"))
      (node (ref "C255") (pin "2") (pinfunction "2_2") (pintype "passive"))
      (node (ref "C256") (pin "2") (pinfunction "2_2") (pintype "passive"))
      (node (ref "C259") (pin "1") (pinfunction "1_1") (pintype "passive"))
      (node (ref "C260") (pin "2") (pinfunction "2_2") (pintype "passive"))
      (node (ref "C264") (pin "2") (pinfunction "2_2") (pintype "passive"))
      (node (ref "C276") (pin "2") (pinfunction "2_2") (pintype "passive"))
      (node (ref "C278") (pin "2") (pinfunction "2_2") (pintype "passive"))
      (node (ref "C280") (pin "2") (pinfunction "2_2") (pintype "passive"))
      (node (ref "R241") (pin "2") (pinfunction "2_2") (pintype "passive"))
    )
    (net (code "12") (name "5V_A") (class "Default")
      (node (ref "C281") (pin "2") (pinfunction "2_2") (pintype "passive"))
      (node (ref "R240") (pin "2") (pinfunction "2_2") (pintype "passive"))
    )
    (net (code "13") (name "24V_PROTECTED") (class "Default")
      (node (ref "C249") (pin "1") (pinfunction "1_1") (pintype "passive"))
      (node (ref "C250") (pin "1") (pinfunction "1_1") (pintype "passive"))
      (node (ref "C251") (pin "2") (pinfunction "2_2") (pintype "passive"))
      (node (ref "C252") (pin "2") (pinfunction "2_2") (pintype "passive"))
      (node (ref "C284") (pin "2") (pinfunction "2_2") (pintype "passive"))
      (node (ref "C285") (pin "2") (pinfunction "2_2") (pintype "passive"))
      (node (ref "R247") (pin "2") (pinfunction "2_2") (pintype "passive"))
    )
    (net (code "14") (name "24V_RAW") (class "Default")
      (node (ref "R249") (pin "2") (pinfunction "2_2") (pintype "passive"))
    )
    (net (code "15") (name "GND") (class "Default")
      (node (ref "C120") (pin "1") (pinfunction "1_1") (pintype "passive"))
      (node (ref "C124") (pin "1") (pinfunction "1_1") (pintype "passive"))
      (node (ref "C247") (pin "2") (pinfunction "2_2") (pintype "passive"))
      (node (ref "C248") (pin "1") (pinfunction "1_1") (pintype "passive"))
      (node (ref "C249") (pin "2") (pinfunction "2_2") (pintype "passive"))
      (node (ref "C250") (pin "2") (pinfunction "2_2") (pintype "passive"))
      (node (ref "C251") (pin "1") (pinfunction "1_1") (pintype "passive"))
      (node (ref "C252") (pin "1") (pinfunction "1_1") (pintype "passive"))
      (node (ref "C253") (pin "2") (pinfunction "2_2") (pintype "passive"))
      (node (ref "C254") (pin "1") (pinfunction "1_1") (pintype "passive"))
      (node (ref "C255") (pin "1") (pinfunction "1_1") (pintype "passive"))
      (node (ref "C256") (pin "1") (pinfunction "1_1") (pintype "passive"))
      (node (ref "C258") (pin "1") (pinfunction "1_1") (pintype "passive"))
      (node (ref "C259") (pin "2") (pinfunction "2_2") (pintype "passive"))
      (node (ref "C260") (pin "1") (pinfunction "1_1") (pintype "passive"))
      (node (ref "C262") (pin "1") (pinfunction "1_1") (pintype "passive"))
      (node (ref "C264") (pin "1") (pinfunction "1_1") (pintype "passive"))
      (node (ref "C266") (pin "1") (pinfunction "1_1") (pintype "passive"))
      (node (ref "C267") (pin "2") (pinfunction "2_2") (pintype "passive"))
      (node (ref "C268") (pin "1") (pinfunction "1_1") (pintype "passive"))
      (node (ref "C269") (pin "1") (pinfunction "1_1") (pintype "passive"))
      (node (ref "C270") (pin "1") (pinfunction "1_1") (pintype "passive"))
      (node (ref "C271") (pin "1") (pinfunction "1_1") (pintype "passive"))
      (node (ref "C272") (pin "1") (pinfunction "1_1") (pintype "passive"))
      (node (ref "C273") (pin "1") (pinfunction "1_1") (pintype "passive"))
      (node (ref "C274") (pin "1") (pinfunction "1_1") (pintype "passive"))
      (node (ref "C275") (pin "1") (pinfunction "1_1") (pintype "passive"))
      (node (ref "C276") (pin "1") (pinfunction "1_1") (pintype "passive"))
      (node (ref "C277") (pin "1") (pinfunction "1_1") (pintype "passive"))
      (node (ref "C278") (pin "1") (pinfunction "1_1") (pintype "passive"))
      (node (ref "C279") (pin "1") (pinfunction "1_1") (pintype "passive"))
      (node (ref "C280") (pin "1") (pinfunction "1_1") (pintype "passive"))
      (node (ref "C281") (pin "1") (pinfunction "1_1") (pintype "passive"))
      (node (ref "C282") (pin "1") (pinfunction "1_1") (pintype "passive"))
      (node (ref "C283") (pin "1") (pinfunction "1_1") (pintype "passive"))
      (node (ref "C284") (pin "1") (pinfunction "1_1") (pintype "passive"))
      (node (ref "C285") (pin "1") (pinfunction "1_1") (pintype "passive"))
      (node (ref "C286") (pin "1") (pinfunction "1_1") (pintype "passive"))
      (node (ref "C287") (pin "1") (pinfunction "1_1") (pintype "passive"))
      (node (ref "C288") (pin "1") (pinfunction "1_1") (pintype "passive"))
      (node (ref "C289") (pin "1") (pinfunction "1_1") (pintype "passive"))
      (node (ref "C290") (pin "1") (pinfunction "1_1") (pintype "passive"))
      (node (ref "C291") (pin "1") (pinfunction "1_1") (pintype "passive"))
      (node (ref "C292") (pin "1") (pinfunction "1_1") (pintype "passive"))
      (node (ref "C293") (pin "1") (pinfunction "1_1") (pintype "passive"))
      (node (ref "C294") (pin "1") (pinfunction "1_1") (pintype "passive"))
      (node (ref "C295") (pin "1") (pinfunction "1_1") (pintype "passive"))
      (node (ref "C296") (pin "1") (pinfunction "1_1") (pintype "passive"))
      (node (ref "C297") (pin "1") (pinfunction "1_1") (pintype "passive"))
      (node (ref "C298") (pin "1") (pinfunction "1_1") (pintype "passive"))
      (node (ref "C299") (pin "1") (pinfunction "1_1") (pintype "passive"))
      (node (ref "C300") (pin "1") (pinfunction "1_1") (pintype "passive"))
      (node (ref "C301") (pin "1") (pinfunction "1_1") (pintype "passive"))
      (node (ref "C302") (pin "1") (pinfunction "1_1") (pintype "passive"))
      (node (ref "C303") (pin "1") (pinfunction "1_1") (pintype "passive"))
      (node (ref "C304") (pin "1") (pinfunction "1_1") (pintype "passive"))
      (node (ref "Q10") (pin "2") (pintype "passive"))
      (node (ref "Q11") (pin "2") (pintype "passive"))
      (node (ref "Q12") (pin "2") (pintype "passive"))
      (node (ref "Q13") (pin "2") (pintype "passive"))
      (node (ref "Q14") (pin "2") (pintype "passive"))
      (node (ref "Q15") (pin "2") (pintype "passive"))
      (node (ref "Q16") (pin "2") (pintype "passive"))
      (node (ref "Q7") (pin "2") (pintype "passive"))
      (node (ref "Q8") (pin "2") (pintype "passive"))
      (node (ref "Q9") (pin "2") (pintype "passive"))
      (node (ref "R252") (pin "1") (pinfunction "1_1") (pintype "passive"))
      (node (ref "R253") (pin "1") (pinfunction "1_1") (pintype "passive"))
    )
    (net (code "16") (name "Net-(D31-PadK)") (class "Default")
      (node (ref "D31") (pin "K") (pinfunction "K_K") (pintype "passive"))
      (node (ref "R230") (pin "2") (pinfunction "2_2") (pintype "passive"))
    )
    (net (code "17") (name "Net-(D32-PadK)") (class "Default")
      (node (ref "D32") (pin "K") (pinfunction "K_K") (pintype "passive"))
      (node (ref "R231") (pin "2") (pinfunction "2_2") (pintype "passive"))
    )
    (net (code "18") (name "Net-(D33-PadK)") (class "Default")
      (node (ref "D33") (pin "K") (pinfunction "K_K") (pintype "passive"))
      (node (ref "R232") (pin "2") (pinfunction "2_2") (pintype "passive"))
    )
    (net (code "19") (name "Net-(D34-PadK)") (class "Default")
      (node (ref "D34") (pin "K") (pinfunction "K_K") (pintype "passive"))
      (node (ref "R233") (pin "2") (pinfunction "2_2") (pintype "passive"))
    )
    (net (code "20") (name "Net-(D35-PadK)") (class "Default")
      (node (ref "D35") (pin "K") (pinfunction "K_K") (pintype "passive"))
      (node (ref "R234") (pin "2") (pinfunction "2_2") (pintype "passive"))
    )
    (net (code "21") (name "Net-(D36-PadK)") (class "Default")
      (node (ref "D36") (pin "K") (pinfunction "K_K") (pintype "passive"))
      (node (ref "R235") (pin "2") (pinfunction "2_2") (pintype "passive"))
    )
    (net (code "22") (name "Net-(D37-PadK)") (class "Default")
      (node (ref "D37") (pin "K") (pinfunction "K_K") (pintype "passive"))
      (node (ref "R236") (pin "2") (pinfunction "2_2") (pintype "passive"))
    )
    (net (code "23") (name "Net-(D38-PadK)") (class "Default")
      (node (ref "D38") (pin "K") (pinfunction "K_K") (pintype "passive"))
      (node (ref "R237") (pin "2") (pinfunction "2_2") (pintype "passive"))
    )
    (net (code "24") (name "Net-(D39-PadK)") (class "Default")
      (node (ref "D39") (pin "K") (pinfunction "K_K") (pintype "passive"))
      (node (ref "R246") (pin "2") (pinfunction "2_2") (pintype "passive"))
    )
    (net (code "25") (name "Net-(D40-PadK)") (class "Default")
      (node (ref "D40") (pin "K") (pinfunction "K_K") (pintype "passive"))
      (node (ref "R248") (pin "2") (pinfunction "2_2") (pintype "passive"))
    )
    (net (code "26") (name "Net-(Q7-Pad1)") (class "Default")
      (node (ref "Q7") (pin "1") (pintype "passive"))
      (node (ref "R238") (pin "1") (pinfunction "1_1") (pintype "passive"))
    )
    (net (code "27") (name "Net-(Q7-Pad3)") (class "Default")
      (node (ref "Q7") (pin "3") (pintype "passive"))
      (node (ref "R230") (pin "1") (pinfunction "1_1") (pintype "passive"))
    )
    (net (code "28") (name "Net-(Q8-Pad1)") (class "Default")
      (node (ref "Q8") (pin "1") (pintype "passive"))
      (node (ref "R239") (pin "1") (pinfunction "1_1") (pintype "passive"))
    )
    (net (code "29") (name "Net-(Q8-Pad3)") (class "Default")
      (node (ref "Q8") (pin "3") (pintype "passive"))
      (node (ref "R231") (pin "1") (pinfunction "1_1") (pintype "passive"))
    )
    (net (code "30") (name "Net-(Q9-Pad1)") (class "Default")
      (node (ref "Q9") (pin "1") (pintype "passive"))
      (node (ref "R240") (pin "1") (pinfunction "1_1") (pintype "passive"))
    )
    (net (code "31") (name "Net-(Q9-Pad3)") (class "Default")
      (node (ref "Q9") (pin "3") (pintype "passive"))
      (node (ref "R232") (pin "1") (pinfunction "1_1") (pintype "passive"))
    )
    (net (code "32") (name "Net-(Q10-Pad1)") (class "Default")
      (node (ref "Q10") (pin "1") (pintype "passive"))
      (node (ref "R241") (pin "1") (pinfunction "1_1") (pintype "passive"))
    )
    (net (code "33") (name "Net-(Q10-Pad3)") (class "Default")
      (node (ref "Q10") (pin "3") (pintype "passive"))
      (node (ref "R233") (pin "1") (pinfunction "1_1") (pintype "passive"))
    )
    (net (code "34") (name "Net-(Q11-Pad1)") (class "Default")
      (node (ref "Q11") (pin "1") (pintype "passive"))
      (node (ref "R242") (pin "1") (pinfunction "1_1") (pintype "passive"))
    )
    (net (code "35") (name "Net-(Q11-Pad3)") (class "Default")
      (node (ref "Q11") (pin "3") (pintype "passive"))
      (node (ref "R234") (pin "1") (pinfunction "1_1") (pintype "passive"))
    )
    (net (code "36") (name "Net-(Q12-Pad1)") (class "Default")
      (node (ref "Q12") (pin "1") (pintype "passive"))
      (node (ref "R243") (pin "1") (pinfunction "1_1") (pintype "passive"))
    )
    (net (code "37") (name "Net-(Q12-Pad3)") (class "Default")
      (node (ref "Q12") (pin "3") (pintype "passive"))
      (node (ref "R235") (pin "1") (pinfunction "1_1") (pintype "passive"))
    )
    (net (code "38") (name "Net-(Q13-Pad1)") (class "Default")
      (node (ref "Q13") (pin "1") (pintype "passive"))
      (node (ref "R244") (pin "1") (pinfunction "1_1") (pintype "passive"))
    )
    (net (code "39") (name "Net-(Q13-Pad3)") (class "Default")
      (node (ref "Q13") (pin "3") (pintype "passive"))
      (node (ref "R236") (pin "1") (pinfunction "1_1") (pintype "passive"))
    )
    (net (code "40") (name "Net-(Q14-Pad1)") (class "Default")
      (node (ref "Q14") (pin "1") (pintype "passive"))
      (node (ref "R245") (pin "1") (pinfunction "1_1") (pintype "passive"))
    )
    (net (code "41") (name "Net-(Q14-Pad3)") (class "Default")
      (node (ref "Q14") (pin "3") (pintype "passive"))
      (node (ref "R237") (pin "1") (pinfunction "1_1") (pintype "passive"))
    )
    (net (code "42") (name "Net-(Q15-Pad1)") (class "Default")
      (node (ref "Q15") (pin "1") (pintype "passive"))
      (node (ref "R250") (pin "1") (pinfunction "1_1") (pintype "passive"))
    )
    (net (code "43") (name "Net-(Q15-Pad3)") (class "Default")
      (node (ref "Q15") (pin "3") (pintype "passive"))
      (node (ref "R246") (pin "1") (pinfunction "1_1") (pintype "passive"))
    )
    (net (code "44") (name "Net-(Q16-Pad1)") (class "Default")
      (node (ref "Q16") (pin "1") (pintype "passive"))
      (node (ref "R251") (pin "1") (pinfunction "1_1") (pintype "passive"))
    )
    (net (code "45") (name "Net-(Q16-Pad3)") (class "Default")
      (node (ref "Q16") (pin "3") (pintype "passive"))
      (node (ref "R248") (pin "1") (pinfunction "1_1") (pintype "passive"))
    )
    (net (code "46") (name "Net-(R247-Pad1)") (class "Default")
      (node (ref "R247") (pin "1") (pinfunction "1_1") (pintype "passive"))
      (node (ref "R250") (pin "2") (pinfunction "2_2") (pintype "passive"))
      (node (ref "R252") (pin "2") (pinfunction "2_2") (pintype "passive"))
    )
    (net (code "47") (name "Net-(R249-Pad1)") (class "Default")
      (node (ref "R249") (pin "1") (pinfunction "1_1") (pintype "passive"))
      (node (ref "R251") (pin "2") (pinfunction "2_2") (pintype "passive"))
      (node (ref "R253") (pin "2") (pinfunction "2_2") (pintype "passive"))
    )
    (net (code "48") (name "VTT") (class "Default")
      (node (ref "C291") (pin "2") (pinfunction "2_2") (pintype "passive"))
      (node (ref "C292") (pin "2") (pinfunction "2_2") (pintype "passive"))
      (node (ref "C293") (pin "2") (pinfunction "2_2") (pintype "passive"))
    )
  )
)
